# LPCB234_-_PI.net
KiCad netlist of a schematic drawn in Altium Designer
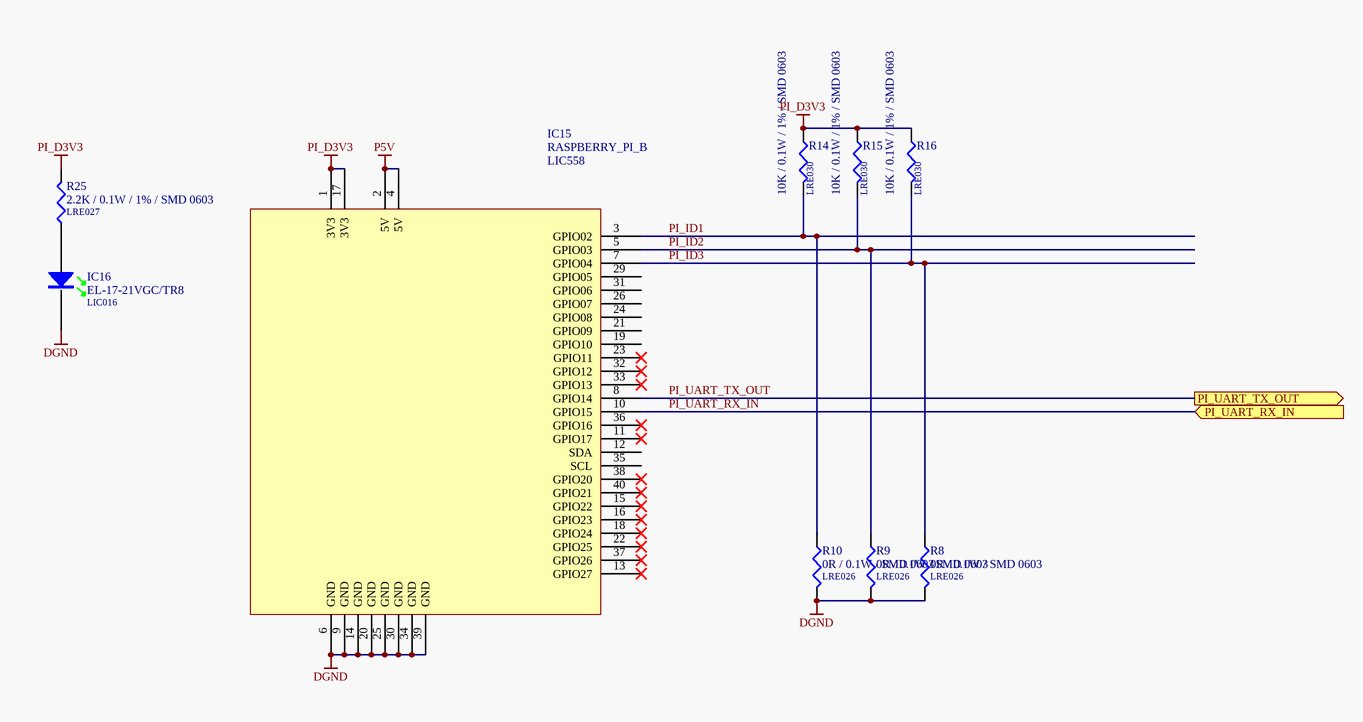
[diagram p0: LPCB234 - PI.SchDoc]

(export (version "E")
  (design (tool "Eeschema 10.0.6"))
  (components
    (comp (ref "IC15")
      (value "RASPBERRY_PI_B")
      (footprint "RASPBERRY_PI_B_VERT")
      (description "Raspberry Pi Model B")
      (fields (field (name "LDL_NUMBER") "LIC558"))
      (libsource (lib "LDL_Semiconductors") (part "RASPBERRY_PI_B"))
    )
    (comp (ref "IC16")
      (value "EL-17-21VGC/TR8")
      (footprint "CR2012-0805-LED")
      (description "LED, SMD, 0805 Green [LIC016]")
      (fields (field (name "LDL_NUMBER") "LIC016"))
      (libsource (lib "LDL_Semiconductors") (part "EL-17-21VGC/TR8"))
    )
    (comp (ref "R8")
      (value "0R / 0.1W / SMD 0603")
      (footprint "LFP020__CR1608-0603-IPC7351_B")
      (description "Resistor, Ceramic Chip, 0R, 0.1W, SMD 0603 [LRE026]")
      (fields (field (name "LDL_NUMBER") "LRE026"))
      (libsource (lib "LDL_Resistors") (part "0R / 0.1W / SMD 0603"))
    )
    (comp (ref "R9")
      (value "0R / 0.1W / SMD 0603")
      (footprint "LFP020__CR1608-0603-IPC7351_B")
      (description "Resistor, Ceramic Chip, 0R, 0.1W, SMD 0603 [LRE026]")
      (fields (field (name "LDL_NUMBER") "LRE026"))
      (libsource (lib "LDL_Resistors") (part "0R / 0.1W / SMD 0603"))
    )
    (comp (ref "R10")
      (value "0R / 0.1W / SMD 0603")
      (footprint "LFP020__CR1608-0603-IPC7351_B")
      (description "Resistor, Ceramic Chip, 0R, 0.1W, SMD 0603 [LRE026]")
      (fields (field (name "LDL_NUMBER") "LRE026"))
      (libsource (lib "LDL_Resistors") (part "0R / 0.1W / SMD 0603"))
    )
    (comp (ref "R14")
      (value "10K / 0.1W / 1% / SMD 0603")
      (footprint "LFP020__CR1608-0603-IPC7351_B")
      (description "Resistor, Ceramic Chip, 10K, 0.1W, 1%, SMD 0603 [LRE030]")
      (fields (field (name "LDL_NUMBER") "LRE030"))
      (libsource (lib "LDL_Resistors") (part "10K / 0.1W / 1% / SMD 0603"))
    )
    (comp (ref "R15")
      (value "10K / 0.1W / 1% / SMD 0603")
      (footprint "LFP020__CR1608-0603-IPC7351_B")
      (description "Resistor, Ceramic Chip, 10K, 0.1W, 1%, SMD 0603 [LRE030]")
      (fields (field (name "LDL_NUMBER") "LRE030"))
      (libsource (lib "LDL_Resistors") (part "10K / 0.1W / 1% / SMD 0603"))
    )
    (comp (ref "R16")
      (value "10K / 0.1W / 1% / SMD 0603")
      (footprint "LFP020__CR1608-0603-IPC7351_B")
      (description "Resistor, Ceramic Chip, 10K, 0.1W, 1%, SMD 0603 [LRE030]")
      (fields (field (name "LDL_NUMBER") "LRE030"))
      (libsource (lib "LDL_Resistors") (part "10K / 0.1W / 1% / SMD 0603"))
    )
    (comp (ref "R25")
      (value "2.2K / 0.1W / 1% / SMD 0603")
      (footprint "LFP020__CR1608-0603-IPC7351_B")
      (description "Resistor, Ceramic Chip, 2.2K, 0.1W, 1%, SMD 0603 [LRE027]")
      (fields (field (name "LDL_NUMBER") "LRE027"))
      (libsource (lib "LDL_Resistors") (part "2.2K / 0.1W / 1% / SMD 0603"))
    )
  )
  (nets
    (net (code "1") (name "/PI_ID1") (class "Default")
      (node (ref "IC15") (pin "3") (pinfunction "GPIO02_3") (pintype "passive"))
      (node (ref "R10") (pin "1") (pintype "passive"))
      (node (ref "R14") (pin "2") (pintype "passive"))
    )
    (net (code "2") (name "/PI_ID2") (class "Default")
      (node (ref "IC15") (pin "5") (pinfunction "GPIO03_5") (pintype "passive"))
      (node (ref "R15") (pin "2") (pintype "passive"))
      (node (ref "R9") (pin "1") (pintype "passive"))
    )
    (net (code "3") (name "/PI_ID3") (class "Default")
      (node (ref "IC15") (pin "7") (pinfunction "GPIO04_7") (pintype "passive"))
      (node (ref "R16") (pin "2") (pintype "passive"))
      (node (ref "R8") (pin "1") (pintype "passive"))
    )
    (net (code "4") (name "/PI_UART_RX_IN") (class "Default")
      (node (ref "IC15") (pin "10") (pinfunction "GPIO15_10") (pintype "passive"))
    )
    (net (code "5") (name "/PI_UART_TX_OUT") (class "Default")
      (node (ref "IC15") (pin "8") (pinfunction "GPIO14_8") (pintype "passive"))
    )
    (net (code "6") (name "DGND") (class "Default")
      (node (ref "IC15") (pin "14") (pinfunction "GND_14") (pintype "power_in"))
      (node (ref "IC15") (pin "20") (pinfunction "GND_20") (pintype "power_in"))
      (node (ref "IC15") (pin "25") (pinfunction "GND_25") (pintype "power_in"))
      (node (ref "IC15") (pin "30") (pinfunction "GND_30") (pintype "power_in"))
      (node (ref "IC15") (pin "34") (pinfunction "GND_34") (pintype "power_in"))
      (node (ref "IC15") (pin "39") (pinfunction "GND_39") (pintype "power_in"))
      (node (ref "IC15") (pin "6") (pinfunction "GND_6") (pintype "power_in"))
      (node (ref "IC15") (pin "9") (pinfunction "GND_9") (pintype "power_in"))
      (node (ref "IC16") (pin "K") (pintype "passive"))
      (node (ref "R10") (pin "2") (pintype "passive"))
      (node (ref "R8") (pin "2") (pintype "passive"))
      (node (ref "R9") (pin "2") (pintype "passive"))
    )
    (net (code "7") (name "Net-(IC16-PadA)") (class "Default")
      (node (ref "IC16") (pin "A") (pintype "passive"))
      (node (ref "R25") (pin "1") (pintype "passive"))
    )
    (net (code "8") (name "P5V") (class "Default")
      (node (ref "IC15") (pin "2") (pinfunction "5V_2") (pintype "power_in"))
      (node (ref "IC15") (pin "4") (pinfunction "5V_4") (pintype "power_in"))
    )
    (net (code "9") (name "PI_D3V3") (class "Default")
      (node (ref "IC15") (pin "1") (pinfunction "3V3_1") (pintype "power_in"))
      (node (ref "IC15") (pin "17") (pinfunction "3V3_17") (pintype "power_in"))
      (node (ref "R14") (pin "1") (pintype "passive"))
      (node (ref "R15") (pin "1") (pintype "passive"))
      (node (ref "R16") (pin "1") (pintype "passive"))
      (node (ref "R25") (pin "2") (pintype "passive"))
    )
    (net (code "10") (name "unconnected-(IC15-GPIO05-Pad29)") (class "Default")
      (node (ref "IC15") (pin "29") (pinfunction "GPIO05_29") (pintype "passive"))
    )
    (net (code "11") (name "unconnected-(IC15-GPIO06-Pad31)") (class "Default")
      (node (ref "IC15") (pin "31") (pinfunction "GPIO06_31") (pintype "passive"))
    )
    (net (code "12") (name "unconnected-(IC15-GPIO07-Pad26)") (class "Default")
      (node (ref "IC15") (pin "26") (pinfunction "GPIO07_26") (pintype "passive"))
    )
    (net (code "13") (name "unconnected-(IC15-GPIO08-Pad24)") (class "Default")
      (node (ref "IC15") (pin "24") (pinfunction "GPIO08_24") (pintype "passive"))
    )
    (net (code "14") (name "unconnected-(IC15-GPIO09-Pad21)") (class "Default")
      (node (ref "IC15") (pin "21") (pinfunction "GPIO09_21") (pintype "passive"))
    )
    (net (code "15") (name "unconnected-(IC15-GPIO10-Pad19)") (class "Default")
      (node (ref "IC15") (pin "19") (pinfunction "GPIO10_19") (pintype "passive"))
    )
    (net (code "16") (name "unconnected-(IC15-GPIO11-Pad23)") (class "Default")
      (node (ref "IC15") (pin "23") (pinfunction "GPIO11_23") (pintype "passive+no_connect"))
    )
    (net (code "17") (name "unconnected-(IC15-GPIO12-Pad32)") (class "Default")
      (node (ref "IC15") (pin "32") (pinfunction "GPIO12_32") (pintype "passive+no_connect"))
    )
    (net (code "18") (name "unconnected-(IC15-GPIO13-Pad33)") (class "Default")
      (node (ref "IC15") (pin "33") (pinfunction "GPIO13_33") (pintype "passive+no_connect"))
    )
    (net (code "19") (name "unconnected-(IC15-GPIO16-Pad36)") (class "Default")
      (node (ref "IC15") (pin "36") (pinfunction "GPIO16_36") (pintype "passive+no_connect"))
    )
    (net (code "20") (name "unconnected-(IC15-GPIO17-Pad11)") (class "Default")
      (node (ref "IC15") (pin "11") (pinfunction "GPIO17_11") (pintype "passive+no_connect"))
    )
    (net (code "21") (name "unconnected-(IC15-GPIO20-Pad38)") (class "Default")
      (node (ref "IC15") (pin "38") (pinfunction "GPIO20_38") (pintype "passive+no_connect"))
    )
    (net (code "22") (name "unconnected-(IC15-GPIO21-Pad40)") (class "Default")
      (node (ref "IC15") (pin "40") (pinfunction "GPIO21_40") (pintype "passive+no_connect"))
    )
    (net (code "23") (name "unconnected-(IC15-GPIO22-Pad15)") (class "Default")
      (node (ref "IC15") (pin "15") (pinfunction "GPIO22_15") (pintype "passive+no_connect"))
    )
    (net (code "24") (name "unconnected-(IC15-GPIO23-Pad16)") (class "Default")
      (node (ref "IC15") (pin "16") (pinfunction "GPIO23_16") (pintype "passive+no_connect"))
    )
    (net (code "25") (name "unconnected-(IC15-GPIO24-Pad18)") (class "Default")
      (node (ref "IC15") (pin "18") (pinfunction "GPIO24_18") (pintype "passive+no_connect"))
    )
    (net (code "26") (name "unconnected-(IC15-GPIO25-Pad22)") (class "Default")
      (node (ref "IC15") (pin "22") (pinfunction "GPIO25_22") (pintype "passive+no_connect"))
    )
    (net (code "27") (name "unconnected-(IC15-GPIO26-Pad37)") (class "Default")
      (node (ref "IC15") (pin "37") (pinfunction "GPIO26_37") (pintype "passive+no_connect"))
    )
    (net (code "28") (name "unconnected-(IC15-GPIO27-Pad13)") (class "Default")
      (node (ref "IC15") (pin "13") (pinfunction "GPIO27_13") (pintype "passive+no_connect"))
    )
    (net (code "29") (name "unconnected-(IC15-SCL-Pad35)") (class "Default")
      (node (ref "IC15") (pin "35") (pinfunction "SCL_35") (pintype "passive"))
    )
    (net (code "30") (name "unconnected-(IC15-SDA-Pad12)") (class "Default")
      (node (ref "IC15") (pin "12") (pinfunction "SDA_12") (pintype "passive"))
    )
  )
)
